# relay_shield.net
KiCad netlist of a schematic drawn in EAGLE
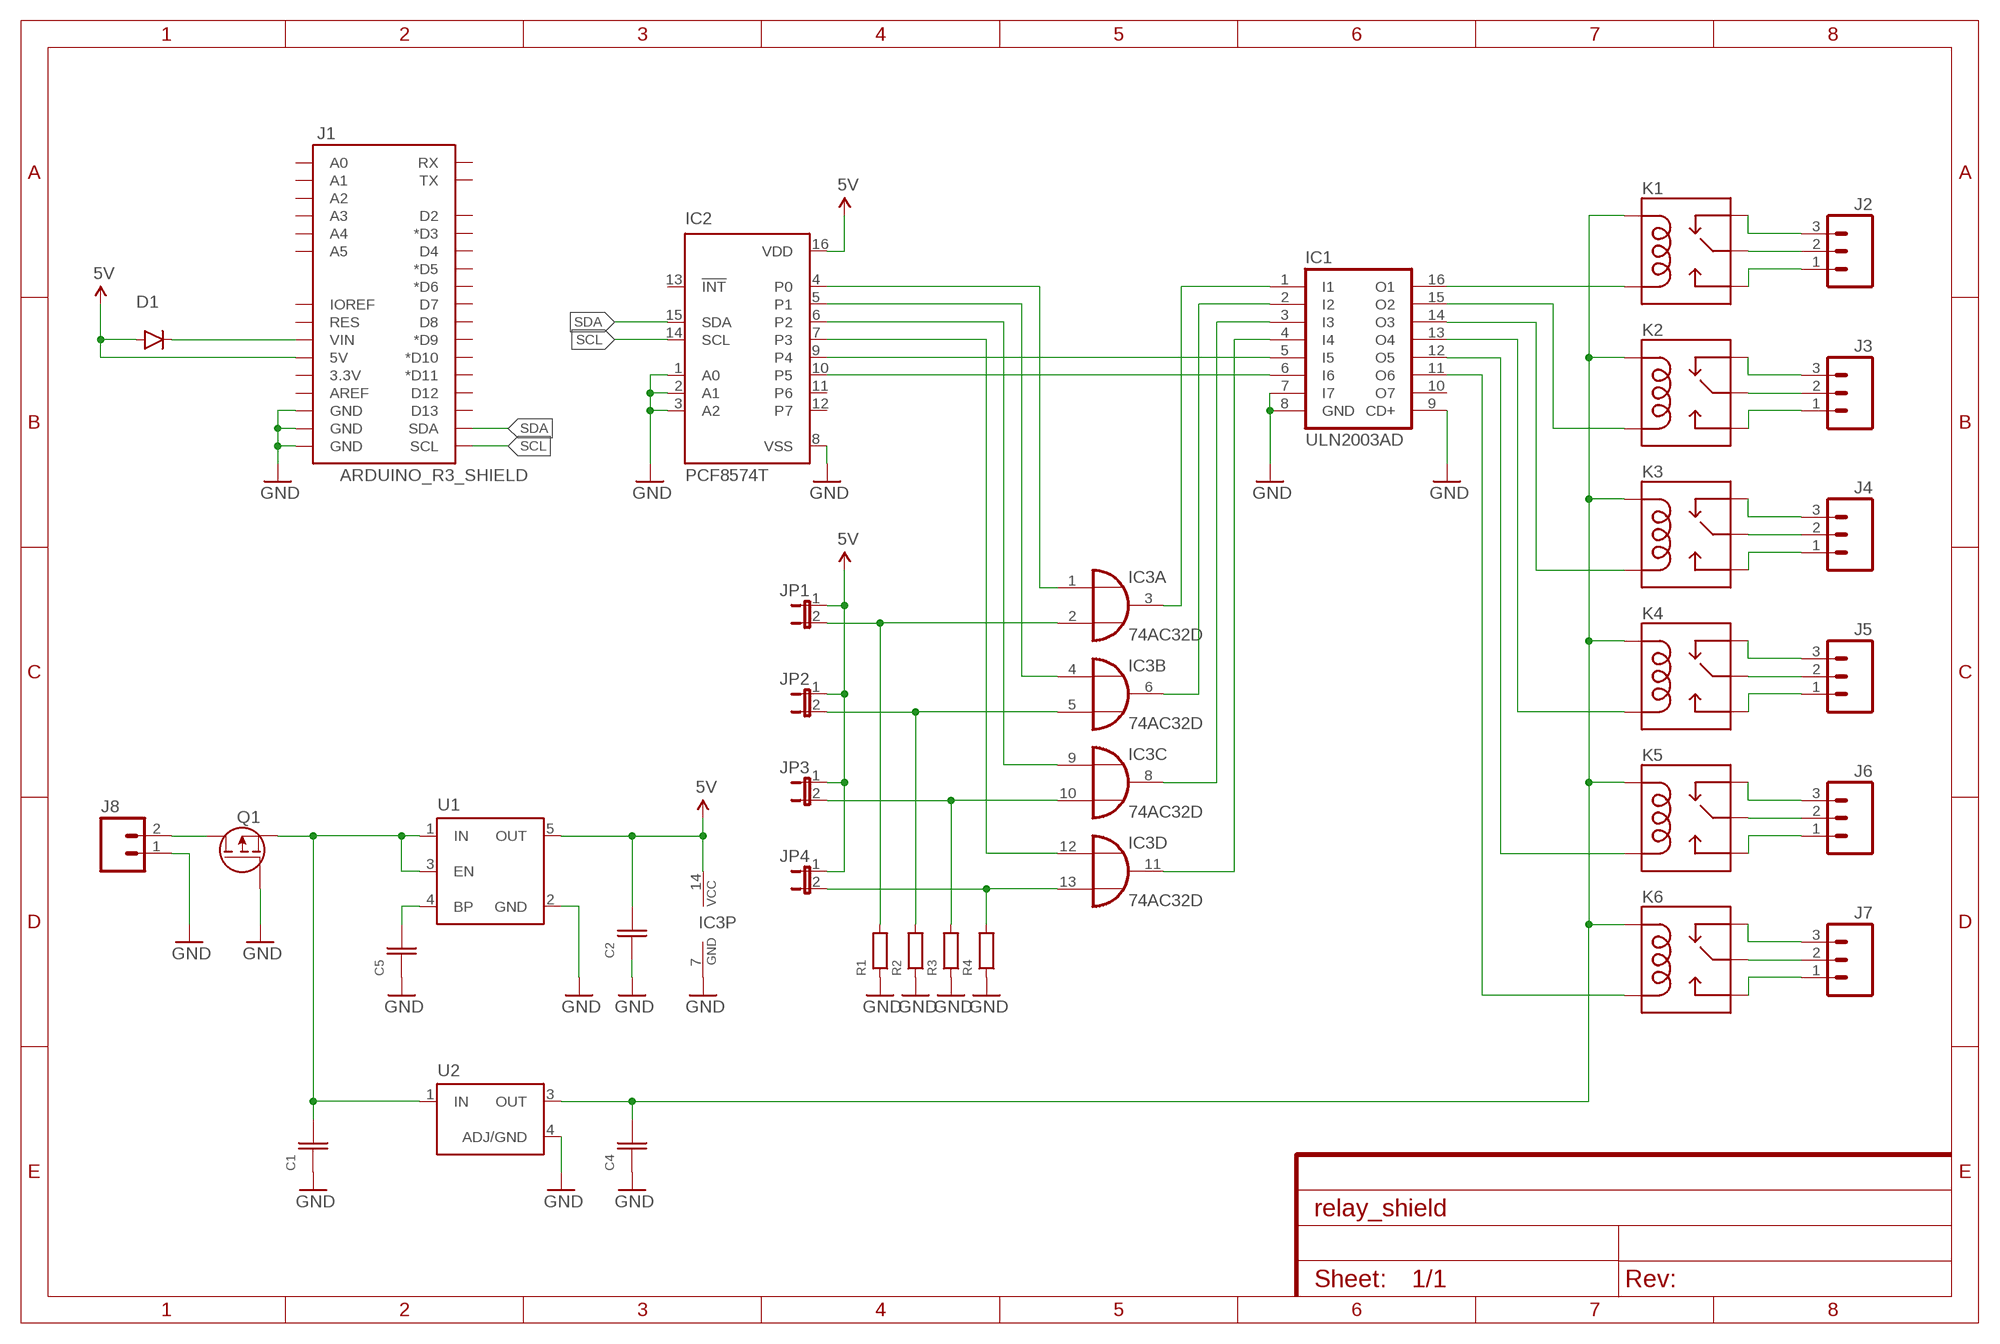
[diagram p0: schematic, sheet 1]

(export (version "E")
  (design (tool "Eeschema 10.0.6"))
  (components
    (comp (ref "C1")
      (value "CAPACITOR_NPOL-1206")
      (footprint "eagle-import:C1206")
      (libsource (lib "eagle-import") (part "CAPACITOR_NPOL-1206"))
    )
    (comp (ref "C2")
      (value "CAPACITOR_NPOL-1206")
      (footprint "eagle-import:C1206")
      (libsource (lib "eagle-import") (part "CAPACITOR_NPOL-1206"))
    )
    (comp (ref "C4")
      (value "CAPACITOR_NPOL-1206")
      (footprint "eagle-import:C1206")
      (libsource (lib "eagle-import") (part "CAPACITOR_NPOL-1206"))
    )
    (comp (ref "C5")
      (value "CAPACITOR_NPOL-0603")
      (footprint "eagle-import:C603")
      (libsource (lib "eagle-import") (part "CAPACITOR_NPOL-0603"))
    )
    (comp (ref "D1")
      (value "DIODE-SOD323")
      (footprint "eagle-import:SOD-323")
      (libsource (lib "eagle-import") (part "DIODE-SOD323"))
    )
    (comp (ref "IC1")
      (value "ULN2003AD")
      (footprint "eagle-import:SO16")
      (libsource (lib "eagle-import") (part "ULN2003AD"))
    )
    (comp (ref "IC2")
      (value "PCF8574T")
      (footprint "eagle-import:SO16W")
      (fields (field (name "MPN") "PCF8574T/3,512"))
      (libsource (lib "eagle-import") (part "PCF8574T"))
    )
    (comp (ref "IC3")
      (value "74AC32D")
      (footprint "eagle-import:SO14")
      (libsource (lib "eagle-import") (part "7432DAC"))
    )
    (comp (ref "J1")
      (value "ARDUINO_R3_SHIELD")
      (footprint "eagle-import:UNO_R3_SHIELD")
      (libsource (lib "eagle-import") (part "ARDUINO_R3_SHIELD"))
    )
    (comp (ref "J2")
      (value "M03SCREW")
      (footprint "eagle-import:SCREWTERMINAL-3.5MM-3")
      (libsource (lib "eagle-import") (part "M03SCREW"))
    )
    (comp (ref "J3")
      (value "M03SCREW")
      (footprint "eagle-import:SCREWTERMINAL-3.5MM-3")
      (libsource (lib "eagle-import") (part "M03SCREW"))
    )
    (comp (ref "J4")
      (value "M03SCREW")
      (footprint "eagle-import:SCREWTERMINAL-3.5MM-3")
      (libsource (lib "eagle-import") (part "M03SCREW"))
    )
    (comp (ref "J5")
      (value "M03SCREW")
      (footprint "eagle-import:SCREWTERMINAL-3.5MM-3")
      (libsource (lib "eagle-import") (part "M03SCREW"))
    )
    (comp (ref "J6")
      (value "M03SCREW")
      (footprint "eagle-import:SCREWTERMINAL-3.5MM-3")
      (libsource (lib "eagle-import") (part "M03SCREW"))
    )
    (comp (ref "J7")
      (value "M03SCREW")
      (footprint "eagle-import:SCREWTERMINAL-3.5MM-3")
      (libsource (lib "eagle-import") (part "M03SCREW"))
    )
    (comp (ref "J8")
      (value "M023.5MM")
      (footprint "eagle-import:SCREWTERMINAL-3.5MM-2")
      (libsource (lib "eagle-import") (part "M023.5MM"))
    )
    (comp (ref "JP1")
      (value "JP1E")
      (footprint "eagle-import:JP1")
      (libsource (lib "eagle-import") (part "JP1E"))
    )
    (comp (ref "JP2")
      (value "JP1E")
      (footprint "eagle-import:JP1")
      (libsource (lib "eagle-import") (part "JP1E"))
    )
    (comp (ref "JP3")
      (value "JP1E")
      (footprint "eagle-import:JP1")
      (libsource (lib "eagle-import") (part "JP1E"))
    )
    (comp (ref "JP4")
      (value "JP1E")
      (footprint "eagle-import:JP1")
      (libsource (lib "eagle-import") (part "JP1E"))
    )
    (comp (ref "K1")
      (value "RELAY-SPDTPTH6")
      (footprint "eagle-import:RELAY-SCHRACK-RY211")
      (libsource (lib "eagle-import") (part "RELAY-SPDTPTH6"))
    )
    (comp (ref "K2")
      (value "RELAY-SPDTPTH6")
      (footprint "eagle-import:RELAY-SCHRACK-RY211")
      (libsource (lib "eagle-import") (part "RELAY-SPDTPTH6"))
    )
    (comp (ref "K3")
      (value "RELAY-SPDTPTH6")
      (footprint "eagle-import:RELAY-SCHRACK-RY211")
      (libsource (lib "eagle-import") (part "RELAY-SPDTPTH6"))
    )
    (comp (ref "K4")
      (value "RELAY-SPDTPTH6")
      (footprint "eagle-import:RELAY-SCHRACK-RY211")
      (libsource (lib "eagle-import") (part "RELAY-SPDTPTH6"))
    )
    (comp (ref "K5")
      (value "RELAY-SPDTPTH6")
      (footprint "eagle-import:RELAY-SCHRACK-RY211")
      (libsource (lib "eagle-import") (part "RELAY-SPDTPTH6"))
    )
    (comp (ref "K6")
      (value "RELAY-SPDTPTH6")
      (footprint "eagle-import:RELAY-SCHRACK-RY211")
      (libsource (lib "eagle-import") (part "RELAY-SPDTPTH6"))
    )
    (comp (ref "Q1")
      (value "MOSFET-P-SOT23-3")
      (footprint "eagle-import:SOT23-3")
      (libsource (lib "eagle-import") (part "MOSFET-P-SOT23-3"))
    )
    (comp (ref "R1")
      (value "RESISTOR-0603")
      (footprint "eagle-import:R0603")
      (libsource (lib "eagle-import") (part "RESISTOR-0603"))
    )
    (comp (ref "R2")
      (value "RESISTOR-0603")
      (footprint "eagle-import:R0603")
      (libsource (lib "eagle-import") (part "RESISTOR-0603"))
    )
    (comp (ref "R3")
      (value "RESISTOR-0603")
      (footprint "eagle-import:R0603")
      (libsource (lib "eagle-import") (part "RESISTOR-0603"))
    )
    (comp (ref "R4")
      (value "RESISTOR-0603")
      (footprint "eagle-import:R0603")
      (libsource (lib "eagle-import") (part "RESISTOR-0603"))
    )
    (comp (ref "U1")
      (value "VREG-5PIN-SOT23")
      (footprint "eagle-import:SOT23-5")
      (libsource (lib "eagle-import") (part "VREG-5PIN-SOT23"))
    )
    (comp (ref "U2")
      (value "VREG-3PIN-DPAK")
      (footprint "eagle-import:DPAK")
      (libsource (lib "eagle-import") (part "VREG-3PIN-DPAK"))
    )
  )
  (nets
    (net (code "1") (name "5V") (class "Default")
      (node (ref "C2") (pin "2") (pinfunction "2_2") (pintype "passive"))
      (node (ref "D1") (pin "A") (pinfunction "A_A") (pintype "passive"))
      (node (ref "IC2") (pin "16") (pinfunction "VDD_16") (pintype "power_in"))
      (node (ref "IC3") (pin "14") (pinfunction "VCC_14") (pintype "power_in"))
      (node (ref "J1") (pin "5V") (pinfunction "5V_5V") (pintype "bidirectional"))
      (node (ref "JP1") (pin "1") (pinfunction "1_1") (pintype "passive"))
      (node (ref "JP2") (pin "1") (pinfunction "1_1") (pintype "passive"))
      (node (ref "JP3") (pin "1") (pinfunction "1_1") (pintype "passive"))
      (node (ref "JP4") (pin "1") (pinfunction "1_1") (pintype "passive"))
      (node (ref "U1") (pin "5") (pinfunction "OUT_5") (pintype "bidirectional"))
    )
    (net (code "2") (name "GND") (class "Default")
      (node (ref "C1") (pin "1") (pinfunction "1_1") (pintype "passive"))
      (node (ref "C2") (pin "1") (pinfunction "1_1") (pintype "passive"))
      (node (ref "C4") (pin "1") (pinfunction "1_1") (pintype "passive"))
      (node (ref "C5") (pin "1") (pinfunction "1_1") (pintype "passive"))
      (node (ref "IC1") (pin "7") (pinfunction "I7_7") (pintype "input"))
      (node (ref "IC1") (pin "8") (pinfunction "GND_8") (pintype "power_in"))
      (node (ref "IC1") (pin "9") (pinfunction "CD+_9") (pintype "passive"))
      (node (ref "IC2") (pin "1") (pinfunction "A0_1") (pintype "input"))
      (node (ref "IC2") (pin "2") (pinfunction "A1_2") (pintype "input"))
      (node (ref "IC2") (pin "3") (pinfunction "A2_3") (pintype "input"))
      (node (ref "IC2") (pin "8") (pinfunction "VSS_8") (pintype "power_in"))
      (node (ref "IC3") (pin "7") (pinfunction "GND_7") (pintype "power_in"))
      (node (ref "J1") (pin "GND@0") (pinfunction "GND_GND@0") (pintype "bidirectional"))
      (node (ref "J1") (pin "GND@1") (pinfunction "GND_GND@1") (pintype "bidirectional"))
      (node (ref "J1") (pin "GND@2") (pinfunction "GND_GND@2") (pintype "bidirectional"))
      (node (ref "J8") (pin "1") (pinfunction "1_1") (pintype "passive"))
      (node (ref "Q1") (pin "1") (pinfunction "G_1") (pintype "passive"))
      (node (ref "R1") (pin "1") (pinfunction "1_1") (pintype "passive"))
      (node (ref "R2") (pin "1") (pinfunction "1_1") (pintype "passive"))
      (node (ref "R3") (pin "1") (pinfunction "1_1") (pintype "passive"))
      (node (ref "R4") (pin "1") (pinfunction "1_1") (pintype "passive"))
      (node (ref "U1") (pin "2") (pinfunction "GND_2") (pintype "bidirectional"))
      (node (ref "U2") (pin "4") (pinfunction "ADJ/GND_4") (pintype "bidirectional"))
    )
    (net (code "3") (name "Net-(D1-PadC)") (class "Default")
      (node (ref "D1") (pin "C") (pinfunction "C_C") (pintype "passive"))
      (node (ref "J1") (pin "VIN") (pinfunction "VIN_VIN") (pintype "bidirectional"))
    )
    (net (code "4") (name "Net-(IC1-I1)") (class "Default")
      (node (ref "IC1") (pin "1") (pinfunction "I1_1") (pintype "input"))
      (node (ref "IC3") (pin "3") (pinfunction "O_3") (pintype "output"))
    )
    (net (code "5") (name "Net-(IC1-I2)") (class "Default")
      (node (ref "IC1") (pin "2") (pinfunction "I2_2") (pintype "input"))
      (node (ref "IC3") (pin "6") (pinfunction "O_6") (pintype "output"))
    )
    (net (code "6") (name "Net-(IC1-I3)") (class "Default")
      (node (ref "IC1") (pin "3") (pinfunction "I3_3") (pintype "input"))
      (node (ref "IC3") (pin "8") (pinfunction "O_8") (pintype "output"))
    )
    (net (code "7") (name "Net-(IC1-I4)") (class "Default")
      (node (ref "IC1") (pin "4") (pinfunction "I4_4") (pintype "input"))
      (node (ref "IC3") (pin "11") (pinfunction "O_11") (pintype "output"))
    )
    (net (code "8") (name "Net-(IC1-I5)") (class "Default")
      (node (ref "IC1") (pin "5") (pinfunction "I5_5") (pintype "input"))
      (node (ref "IC2") (pin "9") (pinfunction "P4_9") (pintype "bidirectional"))
    )
    (net (code "9") (name "Net-(IC1-I6)") (class "Default")
      (node (ref "IC1") (pin "6") (pinfunction "I6_6") (pintype "input"))
      (node (ref "IC2") (pin "10") (pinfunction "P5_10") (pintype "bidirectional"))
    )
    (net (code "10") (name "Net-(IC1-O1)") (class "Default")
      (node (ref "IC1") (pin "16") (pinfunction "O1_16") (pintype "open_collector"))
      (node (ref "K1") (pin "A2") (pinfunction "COIL2_A2") (pintype "bidirectional"))
    )
    (net (code "11") (name "Net-(IC1-O2)") (class "Default")
      (node (ref "IC1") (pin "15") (pinfunction "O2_15") (pintype "open_collector"))
      (node (ref "K2") (pin "A2") (pinfunction "COIL2_A2") (pintype "bidirectional"))
    )
    (net (code "12") (name "Net-(IC1-O3)") (class "Default")
      (node (ref "IC1") (pin "14") (pinfunction "O3_14") (pintype "open_collector"))
      (node (ref "K3") (pin "A2") (pinfunction "COIL2_A2") (pintype "bidirectional"))
    )
    (net (code "13") (name "Net-(IC1-O4)") (class "Default")
      (node (ref "IC1") (pin "13") (pinfunction "O4_13") (pintype "open_collector"))
      (node (ref "K4") (pin "A2") (pinfunction "COIL2_A2") (pintype "bidirectional"))
    )
    (net (code "14") (name "Net-(IC1-O5)") (class "Default")
      (node (ref "IC1") (pin "12") (pinfunction "O5_12") (pintype "open_collector"))
      (node (ref "K5") (pin "A2") (pinfunction "COIL2_A2") (pintype "bidirectional"))
    )
    (net (code "15") (name "Net-(IC1-O6)") (class "Default")
      (node (ref "IC1") (pin "11") (pinfunction "O6_11") (pintype "open_collector"))
      (node (ref "K6") (pin "A2") (pinfunction "COIL2_A2") (pintype "bidirectional"))
    )
    (net (code "16") (name "Net-(IC2-P0)") (class "Default")
      (node (ref "IC2") (pin "4") (pinfunction "P0_4") (pintype "bidirectional"))
      (node (ref "IC3") (pin "1") (pinfunction "I0_1") (pintype "input"))
    )
    (net (code "17") (name "Net-(IC2-P1)") (class "Default")
      (node (ref "IC2") (pin "5") (pinfunction "P1_5") (pintype "bidirectional"))
      (node (ref "IC3") (pin "4") (pinfunction "I0_4") (pintype "input"))
    )
    (net (code "18") (name "Net-(IC2-P2)") (class "Default")
      (node (ref "IC2") (pin "6") (pinfunction "P2_6") (pintype "bidirectional"))
      (node (ref "IC3") (pin "9") (pinfunction "I0_9") (pintype "input"))
    )
    (net (code "19") (name "Net-(IC2-P3)") (class "Default")
      (node (ref "IC2") (pin "7") (pinfunction "P3_7") (pintype "bidirectional"))
      (node (ref "IC3") (pin "12") (pinfunction "I0_12") (pintype "input"))
    )
    (net (code "20") (name "Net-(IC3A-I1)") (class "Default")
      (node (ref "IC3") (pin "2") (pinfunction "I1_2") (pintype "input"))
      (node (ref "JP1") (pin "2") (pinfunction "2_2") (pintype "passive"))
      (node (ref "R1") (pin "2") (pinfunction "2_2") (pintype "passive"))
    )
    (net (code "21") (name "Net-(IC3B-I1)") (class "Default")
      (node (ref "IC3") (pin "5") (pinfunction "I1_5") (pintype "input"))
      (node (ref "JP2") (pin "2") (pinfunction "2_2") (pintype "passive"))
      (node (ref "R2") (pin "2") (pinfunction "2_2") (pintype "passive"))
    )
    (net (code "22") (name "Net-(IC3C-I1)") (class "Default")
      (node (ref "IC3") (pin "10") (pinfunction "I1_10") (pintype "input"))
      (node (ref "JP3") (pin "2") (pinfunction "2_2") (pintype "passive"))
      (node (ref "R3") (pin "2") (pinfunction "2_2") (pintype "passive"))
    )
    (net (code "23") (name "Net-(IC3D-I1)") (class "Default")
      (node (ref "IC3") (pin "13") (pinfunction "I1_13") (pintype "input"))
      (node (ref "JP4") (pin "2") (pinfunction "2_2") (pintype "passive"))
      (node (ref "R4") (pin "2") (pinfunction "2_2") (pintype "passive"))
    )
    (net (code "24") (name "Net-(K1-COIL1)") (class "Default")
      (node (ref "C4") (pin "2") (pinfunction "2_2") (pintype "passive"))
      (node (ref "K1") (pin "A1") (pinfunction "COIL1_A1") (pintype "bidirectional"))
      (node (ref "K2") (pin "A1") (pinfunction "COIL1_A1") (pintype "bidirectional"))
      (node (ref "K3") (pin "A1") (pinfunction "COIL1_A1") (pintype "bidirectional"))
      (node (ref "K4") (pin "A1") (pinfunction "COIL1_A1") (pintype "bidirectional"))
      (node (ref "K5") (pin "A1") (pinfunction "COIL1_A1") (pintype "bidirectional"))
      (node (ref "K6") (pin "A1") (pinfunction "COIL1_A1") (pintype "bidirectional"))
      (node (ref "U2") (pin "3") (pinfunction "OUT_3") (pintype "bidirectional"))
    )
    (net (code "25") (name "Net-(K1-MAIN)") (class "Default")
      (node (ref "J2") (pin "2") (pinfunction "2_2") (pintype "passive"))
      (node (ref "K1") (pin "11") (pinfunction "MAIN_11") (pintype "bidirectional"))
    )
    (net (code "26") (name "Net-(K1-NC)") (class "Default")
      (node (ref "J2") (pin "3") (pinfunction "3_3") (pintype "passive"))
      (node (ref "K1") (pin "12") (pinfunction "NC_12") (pintype "bidirectional"))
    )
    (net (code "27") (name "Net-(K1-NO)") (class "Default")
      (node (ref "J2") (pin "1") (pinfunction "1_1") (pintype "passive"))
      (node (ref "K1") (pin "14") (pinfunction "NO_14") (pintype "bidirectional"))
    )
    (net (code "28") (name "Net-(K2-MAIN)") (class "Default")
      (node (ref "J3") (pin "2") (pinfunction "2_2") (pintype "passive"))
      (node (ref "K2") (pin "11") (pinfunction "MAIN_11") (pintype "bidirectional"))
    )
    (net (code "29") (name "Net-(K2-NC)") (class "Default")
      (node (ref "J3") (pin "3") (pinfunction "3_3") (pintype "passive"))
      (node (ref "K2") (pin "12") (pinfunction "NC_12") (pintype "bidirectional"))
    )
    (net (code "30") (name "Net-(K2-NO)") (class "Default")
      (node (ref "J3") (pin "1") (pinfunction "1_1") (pintype "passive"))
      (node (ref "K2") (pin "14") (pinfunction "NO_14") (pintype "bidirectional"))
    )
    (net (code "31") (name "Net-(K3-MAIN)") (class "Default")
      (node (ref "J4") (pin "2") (pinfunction "2_2") (pintype "passive"))
      (node (ref "K3") (pin "11") (pinfunction "MAIN_11") (pintype "bidirectional"))
    )
    (net (code "32") (name "Net-(K3-NC)") (class "Default")
      (node (ref "J4") (pin "3") (pinfunction "3_3") (pintype "passive"))
      (node (ref "K3") (pin "12") (pinfunction "NC_12") (pintype "bidirectional"))
    )
    (net (code "33") (name "Net-(K3-NO)") (class "Default")
      (node (ref "J4") (pin "1") (pinfunction "1_1") (pintype "passive"))
      (node (ref "K3") (pin "14") (pinfunction "NO_14") (pintype "bidirectional"))
    )
    (net (code "34") (name "Net-(K4-MAIN)") (class "Default")
      (node (ref "J5") (pin "2") (pinfunction "2_2") (pintype "passive"))
      (node (ref "K4") (pin "11") (pinfunction "MAIN_11") (pintype "bidirectional"))
    )
    (net (code "35") (name "Net-(K4-NC)") (class "Default")
      (node (ref "J5") (pin "3") (pinfunction "3_3") (pintype "passive"))
      (node (ref "K4") (pin "12") (pinfunction "NC_12") (pintype "bidirectional"))
    )
    (net (code "36") (name "Net-(K4-NO)") (class "Default")
      (node (ref "J5") (pin "1") (pinfunction "1_1") (pintype "passive"))
      (node (ref "K4") (pin "14") (pinfunction "NO_14") (pintype "bidirectional"))
    )
    (net (code "37") (name "Net-(K5-MAIN)") (class "Default")
      (node (ref "J6") (pin "2") (pinfunction "2_2") (pintype "passive"))
      (node (ref "K5") (pin "11") (pinfunction "MAIN_11") (pintype "bidirectional"))
    )
    (net (code "38") (name "Net-(K5-NC)") (class "Default")
      (node (ref "J6") (pin "3") (pinfunction "3_3") (pintype "passive"))
      (node (ref "K5") (pin "12") (pinfunction "NC_12") (pintype "bidirectional"))
    )
    (net (code "39") (name "Net-(K5-NO)") (class "Default")
      (node (ref "J6") (pin "1") (pinfunction "1_1") (pintype "passive"))
      (node (ref "K5") (pin "14") (pinfunction "NO_14") (pintype "bidirectional"))
    )
    (net (code "40") (name "Net-(K6-MAIN)") (class "Default")
      (node (ref "J7") (pin "2") (pinfunction "2_2") (pintype "passive"))
      (node (ref "K6") (pin "11") (pinfunction "MAIN_11") (pintype "bidirectional"))
    )
    (net (code "41") (name "Net-(K6-NC)") (class "Default")
      (node (ref "J7") (pin "3") (pinfunction "3_3") (pintype "passive"))
      (node (ref "K6") (pin "12") (pinfunction "NC_12") (pintype "bidirectional"))
    )
    (net (code "42") (name "Net-(K6-NO)") (class "Default")
      (node (ref "J7") (pin "1") (pinfunction "1_1") (pintype "passive"))
      (node (ref "K6") (pin "14") (pinfunction "NO_14") (pintype "bidirectional"))
    )
    (net (code "43") (name "Net-(Q1-D)") (class "Default")
      (node (ref "J8") (pin "2") (pinfunction "2_2") (pintype "passive"))
      (node (ref "Q1") (pin "3") (pinfunction "D_3") (pintype "passive"))
    )
    (net (code "44") (name "Net-(Q1-S)") (class "Default")
      (node (ref "C1") (pin "2") (pinfunction "2_2") (pintype "passive"))
      (node (ref "Q1") (pin "2") (pinfunction "S_2") (pintype "passive"))
      (node (ref "U1") (pin "1") (pinfunction "IN_1") (pintype "bidirectional"))
      (node (ref "U1") (pin "3") (pinfunction "EN_3") (pintype "bidirectional"))
      (node (ref "U2") (pin "1") (pinfunction "IN_1") (pintype "bidirectional"))
    )
    (net (code "45") (name "Net-(U1-BP)") (class "Default")
      (node (ref "C5") (pin "2") (pinfunction "2_2") (pintype "passive"))
      (node (ref "U1") (pin "4") (pinfunction "BP_4") (pintype "bidirectional"))
    )
    (net (code "46") (name "SCL") (class "Default")
      (node (ref "IC2") (pin "14") (pinfunction "SCL_14") (pintype "input"))
      (node (ref "J1") (pin "SCL") (pinfunction "SCL_SCL") (pintype "bidirectional"))
    )
    (net (code "47") (name "SDA") (class "Default")
      (node (ref "IC2") (pin "15") (pinfunction "SDA_15") (pintype "bidirectional"))
      (node (ref "J1") (pin "SDA") (pinfunction "SDA_SDA") (pintype "bidirectional"))
    )
    (net (code "48") (name "unconnected-(IC1-O7-Pad10)") (class "Default")
      (node (ref "IC1") (pin "10") (pinfunction "O7_10") (pintype "open_collector"))
    )
    (net (code "49") (name "unconnected-(IC2-P6-Pad11)") (class "Default")
      (node (ref "IC2") (pin "11") (pinfunction "P6_11") (pintype "bidirectional"))
    )
    (net (code "50") (name "unconnected-(IC2-P7-Pad12)") (class "Default")
      (node (ref "IC2") (pin "12") (pinfunction "P7_12") (pintype "bidirectional"))
    )
    (net (code "51") (name "unconnected-(IC2-~{INT}-Pad13)") (class "Default")
      (node (ref "IC2") (pin "13") (pinfunction "~{INT}_13") (pintype "output"))
    )
    (net (code "52") (name "unconnected-(J1-*D3-PadD3)") (class "Default")
      (node (ref "J1") (pin "D3") (pinfunction "*D3_D3") (pintype "bidirectional"))
    )
    (net (code "53") (name "unconnected-(J1-*D5-PadD5)") (class "Default")
      (node (ref "J1") (pin "D5") (pinfunction "*D5_D5") (pintype "bidirectional"))
    )
    (net (code "54") (name "unconnected-(J1-*D6-PadD6)") (class "Default")
      (node (ref "J1") (pin "D6") (pinfunction "*D6_D6") (pintype "bidirectional"))
    )
    (net (code "55") (name "unconnected-(J1-*D9-PadD9)") (class "Default")
      (node (ref "J1") (pin "D9") (pinfunction "*D9_D9") (pintype "bidirectional"))
    )
    (net (code "56") (name "unconnected-(J1-*D10-PadD10)") (class "Default")
      (node (ref "J1") (pin "D10") (pinfunction "*D10_D10") (pintype "bidirectional"))
    )
    (net (code "57") (name "unconnected-(J1-*D11-PadD11)") (class "Default")
      (node (ref "J1") (pin "D11") (pinfunction "*D11_D11") (pintype "bidirectional"))
    )
    (net (code "58") (name "unconnected-(J1-Pad3.3V)") (class "Default")
      (node (ref "J1") (pin "3.3V") (pinfunction "3.3V_3.3V") (pintype "bidirectional"))
    )
    (net (code "59") (name "unconnected-(J1-PadA0)") (class "Default")
      (node (ref "J1") (pin "A0") (pinfunction "A0_A0") (pintype "bidirectional"))
    )
    (net (code "60") (name "unconnected-(J1-PadA1)") (class "Default")
      (node (ref "J1") (pin "A1") (pinfunction "A1_A1") (pintype "bidirectional"))
    )
    (net (code "61") (name "unconnected-(J1-PadA2)") (class "Default")
      (node (ref "J1") (pin "A2") (pinfunction "A2_A2") (pintype "bidirectional"))
    )
    (net (code "62") (name "unconnected-(J1-PadA3)") (class "Default")
      (node (ref "J1") (pin "A3") (pinfunction "A3_A3") (pintype "bidirectional"))
    )
    (net (code "63") (name "unconnected-(J1-PadA4)") (class "Default")
      (node (ref "J1") (pin "A4") (pinfunction "A4_A4") (pintype "bidirectional"))
    )
    (net (code "64") (name "unconnected-(J1-PadA5)") (class "Default")
      (node (ref "J1") (pin "A5") (pinfunction "A5_A5") (pintype "bidirectional"))
    )
    (net (code "65") (name "unconnected-(J1-PadAREF)") (class "Default")
      (node (ref "J1") (pin "AREF") (pinfunction "AREF_AREF") (pintype "bidirectional"))
    )
    (net (code "66") (name "unconnected-(J1-PadD2)") (class "Default")
      (node (ref "J1") (pin "D2") (pinfunction "D2_D2") (pintype "bidirectional"))
    )
    (net (code "67") (name "unconnected-(J1-PadD4)") (class "Default")
      (node (ref "J1") (pin "D4") (pinfunction "D4_D4") (pintype "bidirectional"))
    )
    (net (code "68") (name "unconnected-(J1-PadD7)") (class "Default")
      (node (ref "J1") (pin "D7") (pinfunction "D7_D7") (pintype "bidirectional"))
    )
    (net (code "69") (name "unconnected-(J1-PadD8)") (class "Default")
      (node (ref "J1") (pin "D8") (pinfunction "D8_D8") (pintype "bidirectional"))
    )
    (net (code "70") (name "unconnected-(J1-PadD12)") (class "Default")
      (node (ref "J1") (pin "D12") (pinfunction "D12_D12") (pintype "bidirectional"))
    )
    (net (code "71") (name "unconnected-(J1-PadD13)") (class "Default")
      (node (ref "J1") (pin "D13") (pinfunction "D13_D13") (pintype "bidirectional"))
    )
    (net (code "72") (name "unconnected-(J1-PadIOREF)") (class "Default")
      (node (ref "J1") (pin "IOREF") (pinfunction "IOREF_IOREF") (pintype "bidirectional"))
    )
    (net (code "73") (name "unconnected-(J1-PadRES)") (class "Default")
      (node (ref "J1") (pin "RES") (pinfunction "RES_RES") (pintype "bidirectional"))
    )
    (net (code "74") (name "unconnected-(J1-PadRX)") (class "Default")
      (node (ref "J1") (pin "RX") (pinfunction "RX_RX") (pintype "bidirectional"))
    )
    (net (code "75") (name "unconnected-(J1-PadTX)") (class "Default")
      (node (ref "J1") (pin "TX") (pinfunction "TX_TX") (pintype "bidirectional"))
    )
  )
)
